# AnyPDB.net
KiCad netlist of a schematic drawn in EAGLE
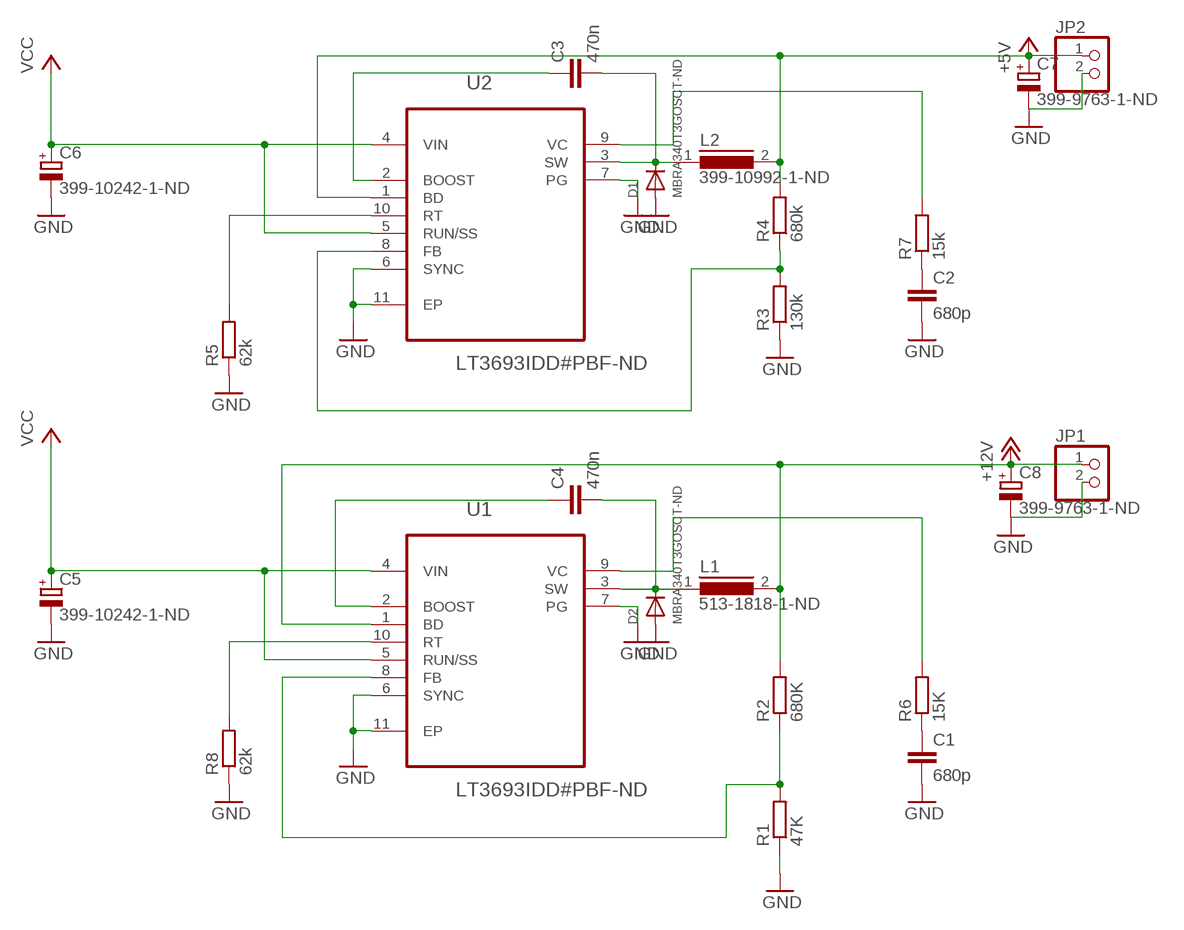
[diagram p0: schematic, sheet 1]

(export (version "E")
  (design (tool "Eeschema 10.0.6"))
  (components
    (comp (ref "C1")
      (value "680p")
      (footprint "eagle-import:C0402K")
      (libsource (lib "eagle-import") (part "C-EUC0402K"))
    )
    (comp (ref "C2")
      (value "680p")
      (footprint "eagle-import:C0402K")
      (libsource (lib "eagle-import") (part "C-EUC0402K"))
    )
    (comp (ref "C3")
      (value "470n")
      (footprint "eagle-import:C0402K")
      (libsource (lib "eagle-import") (part "C-EUC0402K"))
    )
    (comp (ref "C4")
      (value "470n")
      (footprint "eagle-import:C0402K")
      (libsource (lib "eagle-import") (part "C-EUC0402K"))
    )
    (comp (ref "C5")
      (value "399-10242-1-ND")
      (footprint "eagle-import:CT6032")
      (libsource (lib "eagle-import") (part "CPOL-EUCT6032"))
    )
    (comp (ref "C6")
      (value "399-10242-1-ND")
      (footprint "eagle-import:CT6032")
      (libsource (lib "eagle-import") (part "CPOL-EUCT6032"))
    )
    (comp (ref "C7")
      (value "399-9763-1-ND")
      (footprint "eagle-import:CT6032")
      (libsource (lib "eagle-import") (part "CPOL-EUCT6032"))
    )
    (comp (ref "C8")
      (value "399-9763-1-ND")
      (footprint "eagle-import:CT6032")
      (libsource (lib "eagle-import") (part "CPOL-EUCT6032"))
    )
    (comp (ref "D1")
      (value "MBRA340T3GOSCT-ND")
      (footprint "eagle-import:SMADIODE")
      (libsource (lib "eagle-import") (part "DIODESMA"))
    )
    (comp (ref "D2")
      (value "MBRA340T3GOSCT-ND")
      (footprint "eagle-import:SMADIODE")
      (libsource (lib "eagle-import") (part "DIODESMA"))
    )
    (comp (ref "JP1")
      (value "PINHD-1X02_2.54-S")
      (footprint "eagle-import:1X02-S")
      (libsource (lib "eagle-import") (part "PINHD-1X02_2.54-S"))
    )
    (comp (ref "JP2")
      (value "PINHD-1X02_2.54-S")
      (footprint "eagle-import:1X02-S")
      (libsource (lib "eagle-import") (part "PINHD-1X02_2.54-S"))
    )
    (comp (ref "L1")
      (value "513-1818-1-ND")
      (footprint "eagle-import:DR74")
      (libsource (lib "eagle-import") (part "DR74"))
    )
    (comp (ref "L2")
      (value "399-10992-1-ND")
      (footprint "eagle-import:DR74")
      (libsource (lib "eagle-import") (part "DR74"))
    )
    (comp (ref "R1")
      (value "47K")
      (footprint "eagle-import:R0402")
      (libsource (lib "eagle-import") (part "R-EU_R0402"))
    )
    (comp (ref "R2")
      (value "680K")
      (footprint "eagle-import:R0402")
      (libsource (lib "eagle-import") (part "R-EU_R0402"))
    )
    (comp (ref "R3")
      (value "130k")
      (footprint "eagle-import:R0402")
      (libsource (lib "eagle-import") (part "R-EU_R0402"))
    )
    (comp (ref "R4")
      (value "680k")
      (footprint "eagle-import:R0402")
      (libsource (lib "eagle-import") (part "R-EU_R0402"))
    )
    (comp (ref "R5")
      (value "62k")
      (footprint "eagle-import:R0402")
      (libsource (lib "eagle-import") (part "R-EU_R0402"))
    )
    (comp (ref "R6")
      (value "15K")
      (footprint "eagle-import:R0402")
      (libsource (lib "eagle-import") (part "R-EU_R0402"))
    )
    (comp (ref "R7")
      (value "15k")
      (footprint "eagle-import:R0402")
      (libsource (lib "eagle-import") (part "R-EU_R0402"))
    )
    (comp (ref "R8")
      (value "62k")
      (footprint "eagle-import:R0402")
      (libsource (lib "eagle-import") (part "R-EU_R0402"))
    )
    (comp (ref "U1")
      (value "LT3693IDD#PBF-ND")
      (footprint "eagle-import:DFN300X300X80-11N")
      (fields (field (name "MPN") "LT3693IDD#PBF"))
      (libsource (lib "eagle-import") (part "LT3693IDDPBF"))
    )
    (comp (ref "U2")
      (value "LT3693IDD#PBF-ND")
      (footprint "eagle-import:DFN300X300X80-11N")
      (fields (field (name "MPN") "LT3693IDD#PBF"))
      (libsource (lib "eagle-import") (part "LT3693IDDPBF"))
    )
  )
  (nets
    (net (code "1") (name "+5V") (class "Default")
      (node (ref "C7") (pin "+") (pinfunction "+_+") (pintype "passive"))
      (node (ref "JP2") (pin "1") (pinfunction "1_1") (pintype "passive"))
      (node (ref "L2") (pin "2") (pinfunction "2_2") (pintype "passive"))
      (node (ref "R4") (pin "2") (pinfunction "2_2") (pintype "passive"))
      (node (ref "U2") (pin "1") (pinfunction "BD_1") (pintype "input"))
    )
    (net (code "2") (name "+12V") (class "Default")
      (node (ref "C8") (pin "+") (pinfunction "+_+") (pintype "passive"))
      (node (ref "JP1") (pin "1") (pinfunction "1_1") (pintype "passive"))
      (node (ref "L1") (pin "2") (pinfunction "2_2") (pintype "passive"))
      (node (ref "R2") (pin "2") (pinfunction "2_2") (pintype "passive"))
      (node (ref "U1") (pin "1") (pinfunction "BD_1") (pintype "input"))
    )
    (net (code "3") (name "GND") (class "Default")
      (node (ref "C1") (pin "2") (pinfunction "2_2") (pintype "passive"))
      (node (ref "C2") (pin "2") (pinfunction "2_2") (pintype "passive"))
      (node (ref "C5") (pin "-") (pinfunction "-_-") (pintype "passive"))
      (node (ref "C6") (pin "-") (pinfunction "-_-") (pintype "passive"))
      (node (ref "C7") (pin "-") (pinfunction "-_-") (pintype "passive"))
      (node (ref "C8") (pin "-") (pinfunction "-_-") (pintype "passive"))
      (node (ref "D1") (pin "A") (pinfunction "A_A") (pintype "passive"))
      (node (ref "D2") (pin "A") (pinfunction "A_A") (pintype "passive"))
      (node (ref "JP1") (pin "2") (pinfunction "2_2") (pintype "passive"))
      (node (ref "JP2") (pin "2") (pinfunction "2_2") (pintype "passive"))
      (node (ref "R1") (pin "1") (pinfunction "1_1") (pintype "passive"))
      (node (ref "R3") (pin "1") (pinfunction "1_1") (pintype "passive"))
      (node (ref "R5") (pin "1") (pinfunction "1_1") (pintype "passive"))
      (node (ref "R8") (pin "1") (pinfunction "1_1") (pintype "passive"))
      (node (ref "U1") (pin "11") (pinfunction "EP_11") (pintype "passive"))
      (node (ref "U1") (pin "6") (pinfunction "SYNC_6") (pintype "input"))
      (node (ref "U1") (pin "7") (pinfunction "PG_7") (pintype "output"))
      (node (ref "U2") (pin "11") (pinfunction "EP_11") (pintype "passive"))
      (node (ref "U2") (pin "6") (pinfunction "SYNC_6") (pintype "input"))
      (node (ref "U2") (pin "7") (pinfunction "PG_7") (pintype "output"))
    )
    (net (code "4") (name "Net-(C1-Pad1)") (class "Default")
      (node (ref "C1") (pin "1") (pinfunction "1_1") (pintype "passive"))
      (node (ref "R6") (pin "1") (pinfunction "1_1") (pintype "passive"))
    )
    (net (code "5") (name "Net-(C2-Pad1)") (class "Default")
      (node (ref "C2") (pin "1") (pinfunction "1_1") (pintype "passive"))
      (node (ref "R7") (pin "1") (pinfunction "1_1") (pintype "passive"))
    )
    (net (code "6") (name "Net-(U1-BOOST)") (class "Default")
      (node (ref "C4") (pin "1") (pinfunction "1_1") (pintype "passive"))
      (node (ref "U1") (pin "2") (pinfunction "BOOST_2") (pintype "power_in"))
    )
    (net (code "7") (name "Net-(U1-FB)") (class "Default")
      (node (ref "R1") (pin "2") (pinfunction "2_2") (pintype "passive"))
      (node (ref "R2") (pin "1") (pinfunction "1_1") (pintype "passive"))
      (node (ref "U1") (pin "8") (pinfunction "FB_8") (pintype "input"))
    )
    (net (code "8") (name "Net-(U1-RT)") (class "Default")
      (node (ref "R8") (pin "2") (pinfunction "2_2") (pintype "passive"))
      (node (ref "U1") (pin "10") (pinfunction "RT_10") (pintype "input"))
    )
    (net (code "9") (name "Net-(U1-SW)") (class "Default")
      (node (ref "C4") (pin "2") (pinfunction "2_2") (pintype "passive"))
      (node (ref "D2") (pin "C") (pinfunction "C_C") (pintype "passive"))
      (node (ref "L1") (pin "1") (pinfunction "1_1") (pintype "passive"))
      (node (ref "U1") (pin "3") (pinfunction "SW_3") (pintype "output"))
    )
    (net (code "10") (name "Net-(U1-VC)") (class "Default")
      (node (ref "R6") (pin "2") (pinfunction "2_2") (pintype "passive"))
      (node (ref "U1") (pin "9") (pinfunction "VC_9") (pintype "output"))
    )
    (net (code "11") (name "Net-(U2-BOOST)") (class "Default")
      (node (ref "C3") (pin "1") (pinfunction "1_1") (pintype "passive"))
      (node (ref "U2") (pin "2") (pinfunction "BOOST_2") (pintype "power_in"))
    )
    (net (code "12") (name "Net-(U2-FB)") (class "Default")
      (node (ref "R3") (pin "2") (pinfunction "2_2") (pintype "passive"))
      (node (ref "R4") (pin "1") (pinfunction "1_1") (pintype "passive"))
      (node (ref "U2") (pin "8") (pinfunction "FB_8") (pintype "input"))
    )
    (net (code "13") (name "Net-(U2-RT)") (class "Default")
      (node (ref "R5") (pin "2") (pinfunction "2_2") (pintype "passive"))
      (node (ref "U2") (pin "10") (pinfunction "RT_10") (pintype "input"))
    )
    (net (code "14") (name "Net-(U2-SW)") (class "Default")
      (node (ref "C3") (pin "2") (pinfunction "2_2") (pintype "passive"))
      (node (ref "D1") (pin "C") (pinfunction "C_C") (pintype "passive"))
      (node (ref "L2") (pin "1") (pinfunction "1_1") (pintype "passive"))
      (node (ref "U2") (pin "3") (pinfunction "SW_3") (pintype "output"))
    )
    (net (code "15") (name "Net-(U2-VC)") (class "Default")
      (node (ref "R7") (pin "2") (pinfunction "2_2") (pintype "passive"))
      (node (ref "U2") (pin "9") (pinfunction "VC_9") (pintype "output"))
    )
    (net (code "16") (name "VCC") (class "Default")
      (node (ref "C5") (pin "+") (pinfunction "+_+") (pintype "passive"))
      (node (ref "C6") (pin "+") (pinfunction "+_+") (pintype "passive"))
      (node (ref "U1") (pin "4") (pinfunction "VIN_4") (pintype "power_in"))
      (node (ref "U1") (pin "5") (pinfunction "RUN/SS_5") (pintype "input"))
      (node (ref "U2") (pin "4") (pinfunction "VIN_4") (pintype "power_in"))
      (node (ref "U2") (pin "5") (pinfunction "RUN/SS_5") (pintype "input"))
    )
  )
)
